# SCH_SGU-Base.net
KiCad netlist of a schematic drawn in EasyEDA
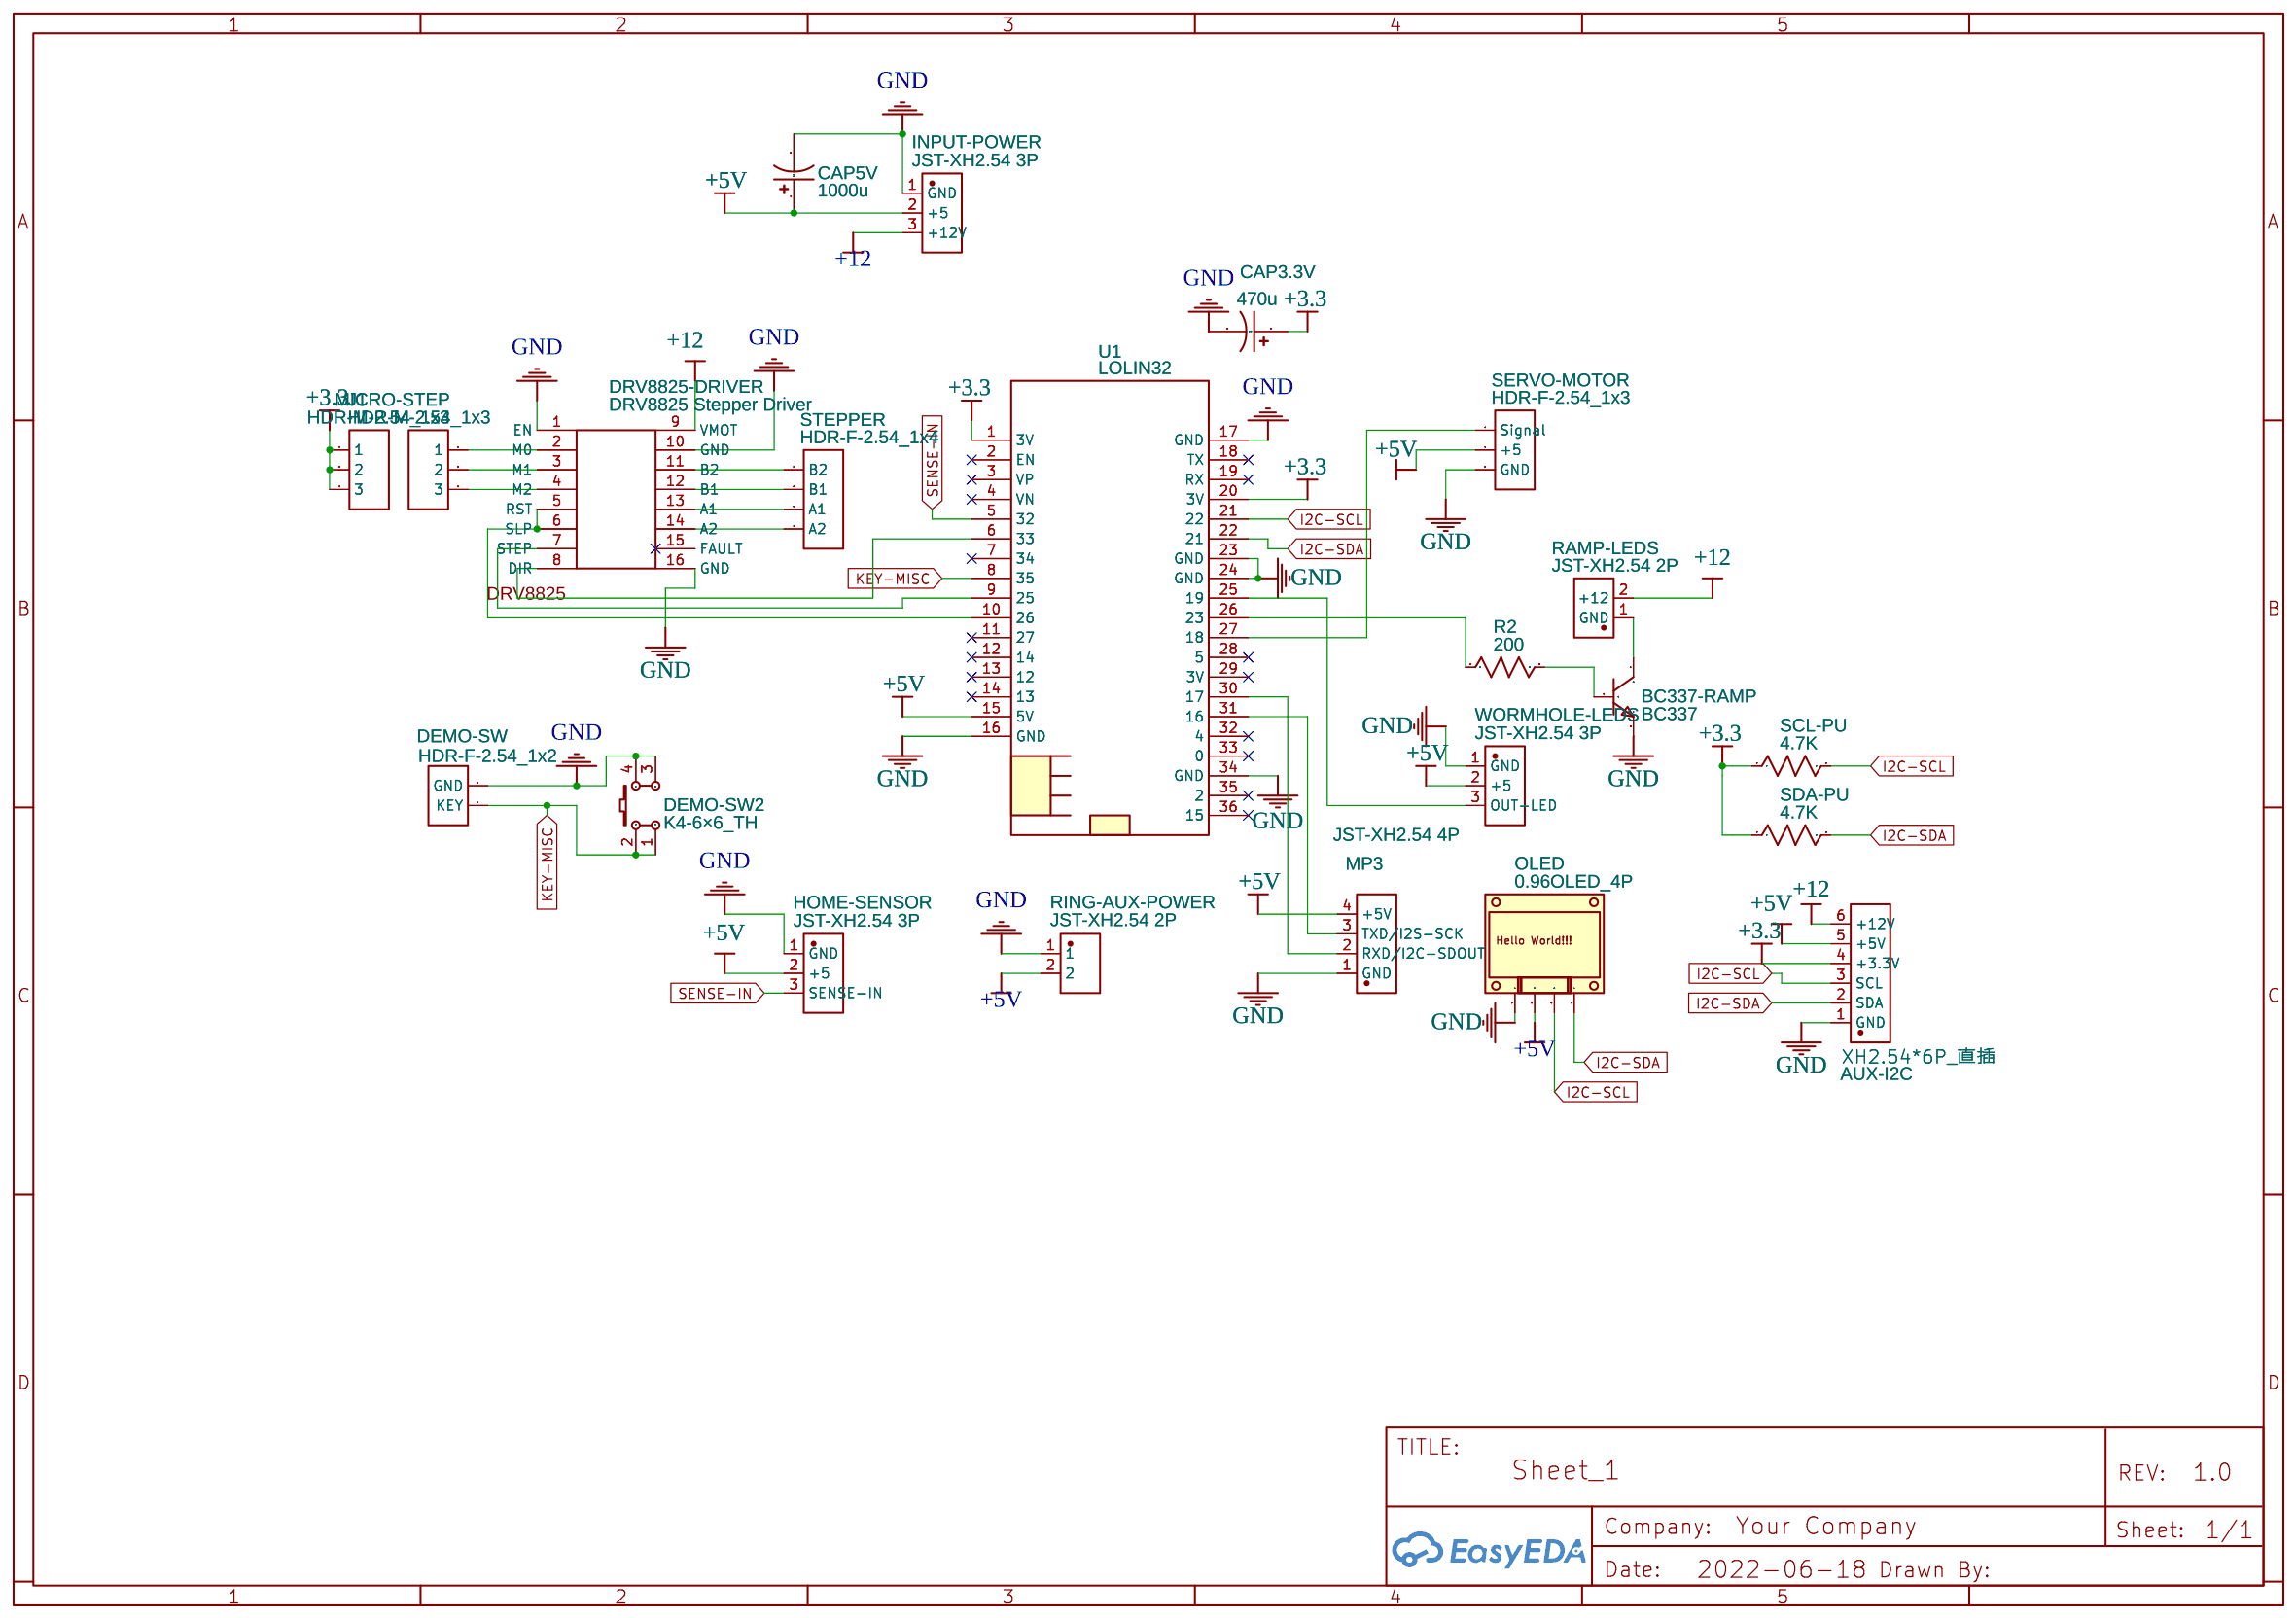
[diagram p0: schematic sheet]

(export (version "E")
  (design (tool "Eeschema 10.0.6"))
  (components
    (comp (ref "AUX-I2C")
      (value "XH2.54*6P_直插")
      (fields (field (name "BOM_Supplier Part") "C9900008614"))
      (libsource (lib "") (part "XH2.54*6P_直插"))
    )
    (comp (ref "BC337-RAMP") (value "BC337") (libsource (lib "") (part "BC337")))
    (comp (ref "CAP3.3V") (value "470u") (libsource (lib "") (part "CE_TH_D4.0×F1.5_US")))
    (comp (ref "CAP5V") (value "1000u") (libsource (lib "") (part "CE_TH_D4.0×F1.5_US_1")))
    (comp (ref "DEMO-SW")
      (value "HDR-F-2.54_1x2")
      (fields (field (name "BOM_Supplier Part") "C49661"))
      (libsource (lib "") (part "HDR-F-2.54_1x2"))
    )
    (comp (ref "DEMO-SW2")
      (value "K4-6×6_TH")
      (fields
        (field (name "BOM_Manufacturer Part") "K2-1102DP-E4SW-04")
        (field (name "BOM_Supplier Part") "C136684")
      )
      (libsource (lib "") (part "K4-6×6_TH"))
    )
    (comp (ref "DRV8825-DRIVER")
      (value "DRV8825 Stepper Driver")
      (libsource (lib "") (part "DRV8825 Stepper Driver"))
    )
    (comp (ref "HOME-SENSOR") (value "JST-XH2.54 3P") (libsource (lib "") (part "JST-XH2.54 3P_1")))
    (comp (ref "INPUT-POWER") (value "JST-XH2.54 3P") (libsource (lib "") (part "JST-XH2.54 3P")))
    (comp (ref "J1")
      (value "HDR-M-2.54_1x3")
      (fields (field (name "BOM_Supplier Part") "C180248"))
      (libsource (lib "") (part "HDR-M-2.54_1x3_1"))
    )
    (comp (ref "MICRO-STEP")
      (value "HDR-M-2.54_1x3")
      (fields (field (name "BOM_Supplier Part") "C180248"))
      (libsource (lib "") (part "HDR-M-2.54_1x3"))
    )
    (comp (ref "MP3") (value "JST-XH2.54 4P") (libsource (lib "") (part "JST-XH2.54 4P")))
    (comp (ref "OLED") (value "0.96OLED_4P") (libsource (lib "") (part "0.96OLED_4P")))
    (comp (ref "R2") (value "200") (libsource (lib "") (part "R_AXIAL-0.3_US")))
    (comp (ref "RAMP-LEDS") (value "JST-XH2.54 2P") (libsource (lib "") (part "JST-XH2.54 2P_1")))
    (comp (ref "RING-AUX-POWER") (value "JST-XH2.54 2P") (libsource (lib "") (part "JST-XH2.54 2P")))
    (comp (ref "SCL-PU") (value "4.7K") (libsource (lib "") (part "R_AXIAL-0.3_US_2")))
    (comp (ref "SDA-PU") (value "4.7K") (libsource (lib "") (part "R_AXIAL-0.3_US_1")))
    (comp (ref "SERVO-MOTOR")
      (value "HDR-F-2.54_1x3")
      (fields (field (name "BOM_Supplier Part") "C146690"))
      (libsource (lib "") (part "HDR-F-2.54_1x3"))
    )
    (comp (ref "STEPPER")
      (value "HDR-F-2.54_1x4")
      (fields (field (name "BOM_Supplier Part") "C225501"))
      (libsource (lib "") (part "HDR-F-2.54_1x4"))
    )
    (comp (ref "U1") (value "LOLIN32") (libsource (lib "") (part "LOLIN32")))
    (comp (ref "WORMHOLE-LEDS") (value "JST-XH2.54 3P") (libsource (lib "") (part "JST-XH2.54 3P_2")))
  )
  (nets
    (net (code "1") (name "+3.3") (class "Default")
      (node (ref "AUX-I2C") (pin "4") (pinfunction "+3.3V_4") (pintype "unspecified"))
      (node (ref "CAP3.3V") (pin "1") (pinfunction "1_1") (pintype "unspecified"))
      (node (ref "J1") (pin "1") (pinfunction "1_1") (pintype "input"))
      (node (ref "J1") (pin "2") (pinfunction "2_2") (pintype "input"))
      (node (ref "J1") (pin "3") (pinfunction "3_3") (pintype "input"))
      (node (ref "SCL-PU") (pin "1") (pinfunction "1_1") (pintype "unspecified"))
      (node (ref "SDA-PU") (pin "1") (pinfunction "1_1") (pintype "unspecified"))
      (node (ref "U1") (pin "1") (pinfunction "3V_1") (pintype "unspecified"))
      (node (ref "U1") (pin "20") (pinfunction "3V_20") (pintype "unspecified"))
    )
    (net (code "2") (name "+5V") (class "Default")
      (node (ref "AUX-I2C") (pin "5") (pinfunction "+5V_5") (pintype "unspecified"))
      (node (ref "CAP5V") (pin "1") (pinfunction "1_1") (pintype "unspecified"))
      (node (ref "HOME-SENSOR") (pin "2") (pinfunction "+5_2") (pintype "unspecified"))
      (node (ref "INPUT-POWER") (pin "2") (pinfunction "+5_2") (pintype "unspecified"))
      (node (ref "MP3") (pin "4") (pinfunction "+5V_4") (pintype "unspecified"))
      (node (ref "OLED") (pin "2") (pinfunction "2_2") (pintype "unspecified"))
      (node (ref "RING-AUX-POWER") (pin "2") (pinfunction "2_2") (pintype "unspecified"))
      (node (ref "SERVO-MOTOR") (pin "2") (pinfunction "+5_2") (pintype "unspecified"))
      (node (ref "U1") (pin "15") (pinfunction "5V_15") (pintype "unspecified"))
      (node (ref "WORMHOLE-LEDS") (pin "2") (pinfunction "+5_2") (pintype "unspecified"))
    )
    (net (code "3") (name "+12") (class "Default")
      (node (ref "AUX-I2C") (pin "6") (pinfunction "+12V_6") (pintype "unspecified"))
      (node (ref "DRV8825-DRIVER") (pin "9") (pinfunction "VMOT_9") (pintype "unspecified"))
      (node (ref "INPUT-POWER") (pin "3") (pinfunction "+12V_3") (pintype "unspecified"))
      (node (ref "RAMP-LEDS") (pin "2") (pinfunction "+12_2") (pintype "unspecified"))
    )
    (net (code "4") (name "GND") (class "Default")
      (node (ref "AUX-I2C") (pin "1") (pinfunction "GND_1") (pintype "unspecified"))
      (node (ref "BC337-RAMP") (pin "3") (pinfunction "E_3") (pintype "unspecified"))
      (node (ref "CAP3.3V") (pin "2") (pinfunction "2_2") (pintype "unspecified"))
      (node (ref "CAP5V") (pin "2") (pinfunction "2_2") (pintype "unspecified"))
      (node (ref "DEMO-SW") (pin "2") (pinfunction "GND_2") (pintype "input"))
      (node (ref "DEMO-SW2") (pin "3") (pinfunction "3_3") (pintype "unspecified"))
      (node (ref "DEMO-SW2") (pin "4") (pinfunction "4_4") (pintype "unspecified"))
      (node (ref "DRV8825-DRIVER") (pin "1") (pinfunction "EN_1") (pintype "unspecified"))
      (node (ref "DRV8825-DRIVER") (pin "10") (pinfunction "GND_10") (pintype "unspecified"))
      (node (ref "DRV8825-DRIVER") (pin "16") (pinfunction "GND_16") (pintype "unspecified"))
      (node (ref "HOME-SENSOR") (pin "1") (pinfunction "GND_1") (pintype "unspecified"))
      (node (ref "INPUT-POWER") (pin "1") (pinfunction "GND_1") (pintype "unspecified"))
      (node (ref "MP3") (pin "1") (pinfunction "GND_1") (pintype "unspecified"))
      (node (ref "OLED") (pin "1") (pinfunction "1_1") (pintype "unspecified"))
      (node (ref "RING-AUX-POWER") (pin "1") (pinfunction "1_1") (pintype "unspecified"))
      (node (ref "SERVO-MOTOR") (pin "3") (pinfunction "GND_3") (pintype "unspecified"))
      (node (ref "U1") (pin "16") (pinfunction "GND_16") (pintype "unspecified"))
      (node (ref "U1") (pin "17") (pinfunction "GND_17") (pintype "unspecified"))
      (node (ref "U1") (pin "23") (pinfunction "GND_23") (pintype "unspecified"))
      (node (ref "U1") (pin "24") (pinfunction "GND_24") (pintype "unspecified"))
      (node (ref "U1") (pin "34") (pinfunction "GND_34") (pintype "unspecified"))
      (node (ref "WORMHOLE-LEDS") (pin "1") (pinfunction "GND_1") (pintype "unspecified"))
    )
    (net (code "5") (name "I2C-SCL") (class "Default")
      (node (ref "AUX-I2C") (pin "3") (pinfunction "SCL_3") (pintype "unspecified"))
      (node (ref "OLED") (pin "3") (pinfunction "3_3") (pintype "unspecified"))
      (node (ref "SCL-PU") (pin "2") (pinfunction "2_2") (pintype "unspecified"))
      (node (ref "U1") (pin "21") (pinfunction "22_21") (pintype "unspecified"))
    )
    (net (code "6") (name "I2C-SDA") (class "Default")
      (node (ref "AUX-I2C") (pin "2") (pinfunction "SDA_2") (pintype "unspecified"))
      (node (ref "OLED") (pin "4") (pinfunction "4_4") (pintype "unspecified"))
      (node (ref "SDA-PU") (pin "2") (pinfunction "2_2") (pintype "unspecified"))
      (node (ref "U1") (pin "22") (pinfunction "21_22") (pintype "unspecified"))
    )
    (net (code "7") (name "KEY-MISC") (class "Default")
      (node (ref "DEMO-SW") (pin "1") (pinfunction "KEY_1") (pintype "input"))
      (node (ref "DEMO-SW2") (pin "1") (pinfunction "1_1") (pintype "unspecified"))
      (node (ref "DEMO-SW2") (pin "2") (pinfunction "2_2") (pintype "unspecified"))
      (node (ref "U1") (pin "8") (pinfunction "35_8") (pintype "unspecified"))
    )
    (net (code "8") (name "Net-(BC337-RAMP-B)") (class "Default")
      (node (ref "BC337-RAMP") (pin "2") (pinfunction "B_2") (pintype "unspecified"))
      (node (ref "R2") (pin "2") (pinfunction "2_2") (pintype "unspecified"))
    )
    (net (code "9") (name "Net-(BC337-RAMP-C)") (class "Default")
      (node (ref "BC337-RAMP") (pin "1") (pinfunction "C_1") (pintype "unspecified"))
      (node (ref "RAMP-LEDS") (pin "1") (pinfunction "GND_1") (pintype "unspecified"))
    )
    (net (code "10") (name "Net-(DRV8825-DRIVER-A1)") (class "Default")
      (node (ref "DRV8825-DRIVER") (pin "13") (pinfunction "A1_13") (pintype "unspecified"))
      (node (ref "STEPPER") (pin "3") (pinfunction "A1_3") (pintype "unspecified"))
    )
    (net (code "11") (name "Net-(DRV8825-DRIVER-A2)") (class "Default")
      (node (ref "DRV8825-DRIVER") (pin "14") (pinfunction "A2_14") (pintype "unspecified"))
      (node (ref "STEPPER") (pin "4") (pinfunction "A2_4") (pintype "unspecified"))
    )
    (net (code "12") (name "Net-(DRV8825-DRIVER-B1)") (class "Default")
      (node (ref "DRV8825-DRIVER") (pin "12") (pinfunction "B1_12") (pintype "unspecified"))
      (node (ref "STEPPER") (pin "2") (pinfunction "B1_2") (pintype "unspecified"))
    )
    (net (code "13") (name "Net-(DRV8825-DRIVER-B2)") (class "Default")
      (node (ref "DRV8825-DRIVER") (pin "11") (pinfunction "B2_11") (pintype "unspecified"))
      (node (ref "STEPPER") (pin "1") (pinfunction "B2_1") (pintype "unspecified"))
    )
    (net (code "14") (name "Net-(DRV8825-DRIVER-DIR)") (class "Default")
      (node (ref "DRV8825-DRIVER") (pin "8") (pinfunction "DIR_8") (pintype "unspecified"))
      (node (ref "U1") (pin "6") (pinfunction "33_6") (pintype "unspecified"))
    )
    (net (code "15") (name "Net-(DRV8825-DRIVER-M0)") (class "Default")
      (node (ref "DRV8825-DRIVER") (pin "2") (pinfunction "M0_2") (pintype "unspecified"))
      (node (ref "MICRO-STEP") (pin "1") (pinfunction "1_1") (pintype "input"))
    )
    (net (code "16") (name "Net-(DRV8825-DRIVER-M1)") (class "Default")
      (node (ref "DRV8825-DRIVER") (pin "3") (pinfunction "M1_3") (pintype "unspecified"))
      (node (ref "MICRO-STEP") (pin "2") (pinfunction "2_2") (pintype "input"))
    )
    (net (code "17") (name "Net-(DRV8825-DRIVER-M2)") (class "Default")
      (node (ref "DRV8825-DRIVER") (pin "4") (pinfunction "M2_4") (pintype "unspecified"))
      (node (ref "MICRO-STEP") (pin "3") (pinfunction "3_3") (pintype "input"))
    )
    (net (code "18") (name "Net-(DRV8825-DRIVER-RST)") (class "Default")
      (node (ref "DRV8825-DRIVER") (pin "5") (pinfunction "RST_5") (pintype "unspecified"))
      (node (ref "DRV8825-DRIVER") (pin "6") (pinfunction "SLP_6") (pintype "unspecified"))
      (node (ref "U1") (pin "10") (pinfunction "26_10") (pintype "unspecified"))
    )
    (net (code "19") (name "Net-(DRV8825-DRIVER-STEP)") (class "Default")
      (node (ref "DRV8825-DRIVER") (pin "7") (pinfunction "STEP_7") (pintype "unspecified"))
      (node (ref "U1") (pin "9") (pinfunction "25_9") (pintype "unspecified"))
    )
    (net (code "20") (name "Net-(MP3-RXD{slash}I2C-SDOUT)") (class "Default")
      (node (ref "MP3") (pin "2") (pinfunction "RXD/I2C-SDOUT_2") (pintype "unspecified"))
      (node (ref "U1") (pin "30") (pinfunction "17_30") (pintype "unspecified"))
    )
    (net (code "21") (name "Net-(MP3-TXD{slash}I2S-SCK)") (class "Default")
      (node (ref "MP3") (pin "3") (pinfunction "TXD/I2S-SCK_3") (pintype "unspecified"))
      (node (ref "U1") (pin "31") (pinfunction "16_31") (pintype "unspecified"))
    )
    (net (code "22") (name "Net-(SERVO-MOTOR-Signal)") (class "Default")
      (node (ref "SERVO-MOTOR") (pin "1") (pinfunction "Signal_1") (pintype "unspecified"))
      (node (ref "U1") (pin "27") (pinfunction "18_27") (pintype "unspecified"))
    )
    (net (code "23") (name "Net-(U1-19)") (class "Default")
      (node (ref "U1") (pin "25") (pinfunction "19_25") (pintype "unspecified"))
      (node (ref "WORMHOLE-LEDS") (pin "3") (pinfunction "OUT-LED_3") (pintype "unspecified"))
    )
    (net (code "24") (name "Net-(U1-23)") (class "Default")
      (node (ref "R2") (pin "1") (pinfunction "1_1") (pintype "unspecified"))
      (node (ref "U1") (pin "26") (pinfunction "23_26") (pintype "unspecified"))
    )
    (net (code "25") (name "SENSE-IN") (class "Default")
      (node (ref "HOME-SENSOR") (pin "3") (pinfunction "SENSE-IN_3") (pintype "unspecified"))
      (node (ref "U1") (pin "5") (pinfunction "32_5") (pintype "unspecified"))
    )
    (net (code "26") (name "unconnected-(DRV8825-DRIVER-FAULT-Pad15)") (class "Default")
      (node (ref "DRV8825-DRIVER") (pin "15") (pinfunction "FAULT_15") (pintype "unspecified+no_connect"))
    )
    (net (code "27") (name "unconnected-(U1-0-Pad33)") (class "Default")
      (node (ref "U1") (pin "33") (pinfunction "0_33") (pintype "unspecified+no_connect"))
    )
    (net (code "28") (name "unconnected-(U1-2-Pad35)") (class "Default")
      (node (ref "U1") (pin "35") (pinfunction "2_35") (pintype "unspecified+no_connect"))
    )
    (net (code "29") (name "unconnected-(U1-3V-Pad29)") (class "Default")
      (node (ref "U1") (pin "29") (pinfunction "3V_29") (pintype "unspecified+no_connect"))
    )
    (net (code "30") (name "unconnected-(U1-4-Pad32)") (class "Default")
      (node (ref "U1") (pin "32") (pinfunction "4_32") (pintype "unspecified+no_connect"))
    )
    (net (code "31") (name "unconnected-(U1-5-Pad28)") (class "Default")
      (node (ref "U1") (pin "28") (pinfunction "5_28") (pintype "unspecified+no_connect"))
    )
    (net (code "32") (name "unconnected-(U1-12-Pad13)") (class "Default")
      (node (ref "U1") (pin "13") (pinfunction "12_13") (pintype "unspecified+no_connect"))
    )
    (net (code "33") (name "unconnected-(U1-13-Pad14)") (class "Default")
      (node (ref "U1") (pin "14") (pinfunction "13_14") (pintype "unspecified+no_connect"))
    )
    (net (code "34") (name "unconnected-(U1-14-Pad12)") (class "Default")
      (node (ref "U1") (pin "12") (pinfunction "14_12") (pintype "unspecified+no_connect"))
    )
    (net (code "35") (name "unconnected-(U1-15-Pad36)") (class "Default")
      (node (ref "U1") (pin "36") (pinfunction "15_36") (pintype "unspecified+no_connect"))
    )
    (net (code "36") (name "unconnected-(U1-27-Pad11)") (class "Default")
      (node (ref "U1") (pin "11") (pinfunction "27_11") (pintype "unspecified+no_connect"))
    )
    (net (code "37") (name "unconnected-(U1-34-Pad7)") (class "Default")
      (node (ref "U1") (pin "7") (pinfunction "34_7") (pintype "unspecified+no_connect"))
    )
    (net (code "38") (name "unconnected-(U1-EN-Pad2)") (class "Default")
      (node (ref "U1") (pin "2") (pinfunction "EN_2") (pintype "unspecified+no_connect"))
    )
    (net (code "39") (name "unconnected-(U1-RX-Pad19)") (class "Default")
      (node (ref "U1") (pin "19") (pinfunction "RX_19") (pintype "unspecified+no_connect"))
    )
    (net (code "40") (name "unconnected-(U1-TX-Pad18)") (class "Default")
      (node (ref "U1") (pin "18") (pinfunction "TX_18") (pintype "unspecified+no_connect"))
    )
    (net (code "41") (name "unconnected-(U1-VN-Pad4)") (class "Default")
      (node (ref "U1") (pin "4") (pinfunction "VN_4") (pintype "unspecified+no_connect"))
    )
    (net (code "42") (name "unconnected-(U1-VP-Pad3)") (class "Default")
      (node (ref "U1") (pin "3") (pinfunction "VP_3") (pintype "unspecified+no_connect"))
    )
  )
)
